# Pcb.net
KiCad netlist of a schematic drawn in EAGLE
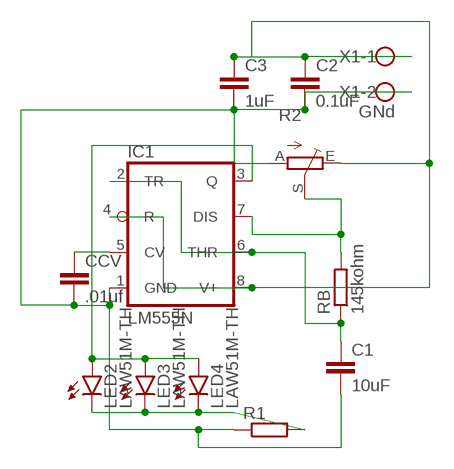
[diagram p0: schematic, sheet 1]

(export (version "E")
  (design (tool "Eeschema 10.0.6"))
  (components
    (comp (ref "C1")
      (value "10uF")
      (footprint "eagle-import:C2.5-2")
      (libsource (lib "eagle-import") (part "C2.5/2"))
    )
    (comp (ref "C2")
      (value "0.1uF")
      (footprint "eagle-import:C025-024X044")
      (libsource (lib "eagle-import") (part "C-EU025-024X044"))
    )
    (comp (ref "C3")
      (value "1uF")
      (footprint "eagle-import:C2.5-2")
      (libsource (lib "eagle-import") (part "C2.5/2"))
    )
    (comp (ref "CCV")
      (value ".01uf")
      (footprint "eagle-import:C2.5-2")
      (libsource (lib "eagle-import") (part "C2.5/2"))
    )
    (comp (ref "IC1")
      (value "LM555N")
      (footprint "eagle-import:DIL08")
      (libsource (lib "eagle-import") (part "555NLM"))
    )
    (comp (ref "LED2")
      (value "LAW51M-TH")
      (footprint "eagle-import:W51-COOL")
      (libsource (lib "eagle-import") (part "W51M-THLA"))
    )
    (comp (ref "LED3")
      (value "LAW51M-TH")
      (footprint "eagle-import:W51-COOL")
      (libsource (lib "eagle-import") (part "W51M-THLA"))
    )
    (comp (ref "LED4")
      (value "LAW51M-TH")
      (footprint "eagle-import:W51-COOL")
      (libsource (lib "eagle-import") (part "W51M-THLA"))
    )
    (comp (ref "R1")
      (value "R-EU_0309/12")
      (footprint "eagle-import:0309_12")
      (libsource (lib "eagle-import") (part "R-EU_0309/12"))
    )
    (comp (ref "R2")
      (value "TRIM_EU-B25P")
      (footprint "eagle-import:B25P")
      (libsource (lib "eagle-import") (part "TRIM_EU-B25P"))
    )
    (comp (ref "RB")
      (value "145kohm")
      (footprint "eagle-import:0309_12")
      (libsource (lib "eagle-import") (part "R-EU_0309/12"))
    )
    (comp (ref "X1")
      (value "GNd")
      (footprint "eagle-import:W237-102")
      (fields (field (name "MPN") "237-102"))
      (libsource (lib "eagle-import") (part "W237-102"))
    )
  )
  (nets
    (net (code "1") (name "Net-(IC1-CV)") (class "Default")
      (node (ref "CCV") (pin "1") (pinfunction "1_1") (pintype "passive"))
      (node (ref "IC1") (pin "5") (pinfunction "CV_5") (pintype "input"))
    )
    (net (code "2") (name "Net-(IC1-DIS)") (class "Default")
      (node (ref "IC1") (pin "7") (pinfunction "DIS_7") (pintype "input"))
      (node (ref "R2") (pin "S") (pinfunction "S_S") (pintype "passive"))
      (node (ref "RB") (pin "2") (pinfunction "2_2") (pintype "passive"))
    )
    (net (code "3") (name "Net-(IC1-GND)") (class "Default")
      (node (ref "C1") (pin "2") (pinfunction "2_2") (pintype "passive"))
      (node (ref "C2") (pin "2") (pinfunction "2_2") (pintype "passive"))
      (node (ref "C3") (pin "2") (pinfunction "2_2") (pintype "passive"))
      (node (ref "CCV") (pin "2") (pinfunction "2_2") (pintype "passive"))
      (node (ref "IC1") (pin "1") (pinfunction "GND_1") (pintype "power_in"))
      (node (ref "R1") (pin "1") (pinfunction "1_1") (pintype "passive"))
      (node (ref "R2") (pin "A") (pinfunction "A_A") (pintype "passive"))
      (node (ref "X1") (pin "2") (pinfunction "KL_2") (pintype "passive"))
    )
    (net (code "4") (name "Net-(IC1-Q)") (class "Default")
      (node (ref "IC1") (pin "3") (pinfunction "Q_3") (pintype "output"))
      (node (ref "LED2") (pin "A") (pinfunction "A_A") (pintype "passive"))
      (node (ref "LED3") (pin "A") (pinfunction "A_A") (pintype "passive"))
      (node (ref "LED4") (pin "A") (pinfunction "A_A") (pintype "passive"))
    )
    (net (code "5") (name "Net-(IC1-R)") (class "Default")
      (node (ref "C2") (pin "1") (pinfunction "1_1") (pintype "passive"))
      (node (ref "C3") (pin "1") (pinfunction "1_1") (pintype "passive"))
      (node (ref "IC1") (pin "4") (pinfunction "R_4") (pintype "input"))
      (node (ref "IC1") (pin "8") (pinfunction "V+_8") (pintype "power_in"))
      (node (ref "R2") (pin "E") (pinfunction "E_E") (pintype "passive"))
      (node (ref "X1") (pin "1") (pinfunction "KL_1") (pintype "passive"))
    )
    (net (code "6") (name "Net-(IC1-THR)") (class "Default")
      (node (ref "C1") (pin "1") (pinfunction "1_1") (pintype "passive"))
      (node (ref "IC1") (pin "2") (pinfunction "TR_2") (pintype "input"))
      (node (ref "IC1") (pin "6") (pinfunction "THR_6") (pintype "input"))
      (node (ref "RB") (pin "1") (pinfunction "1_1") (pintype "passive"))
    )
    (net (code "7") (name "Net-(LED2-PadC)") (class "Default")
      (node (ref "LED2") (pin "C") (pinfunction "C_C") (pintype "passive"))
      (node (ref "LED3") (pin "C") (pinfunction "C_C") (pintype "passive"))
      (node (ref "LED4") (pin "C") (pinfunction "C_C") (pintype "passive"))
      (node (ref "R1") (pin "2") (pinfunction "2_2") (pintype "passive"))
    )
  )
)
